# RS485.net
KiCad netlist of a schematic drawn in Altium Designer
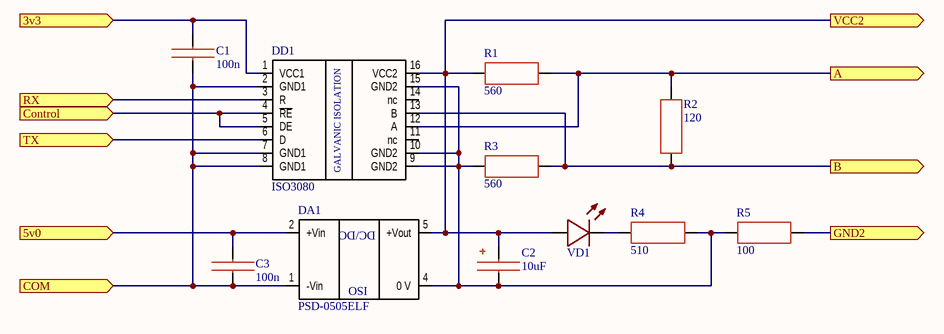
[diagram p0: RS485.SchDoc]

(export (version "E")
  (design (tool "Eeschema 10.0.6"))
  (components
    (comp (ref "C1")
      (value "100n")
      (footprint "Capacitor:CC0805_3D")
      (libsource (lib "Capacitor") (part "CC0805 X uF"))
    )
    (comp (ref "C2")
      (value "10uF")
      (footprint "Tantal Type C")
      (description "16 V")
      (libsource (lib "Capacitor") (part "Tantal C 10uF"))
    )
    (comp (ref "C3")
      (value "100n")
      (footprint "Capacitor:CC0805_3D")
      (libsource (lib "Capacitor") (part "CC0805 X uF"))
    )
    (comp (ref "DA1")
      (value "PSD-0505ELF")
      (footprint "PSD-xxxxELF")
      (description "PSD-xxxxELF")
      (libsource (lib "Rus_Library") (part "PSD-xxxxELF"))
    )
    (comp (ref "DD1")
      (value "ISO3080")
      (footprint "SO_16_W")
      (libsource (lib "Rus_Library") (part "ISO3080"))
    )
    (comp (ref "R1")
      (value "560")
      (footprint "Resistor:RC0805_3D")
      (libsource (lib "Resistor") (part "RC0805 X Ohm"))
    )
    (comp (ref "R2")
      (value "120")
      (footprint "Resistor:RC0805_3D")
      (libsource (lib "Resistor") (part "RC0805 X Ohm"))
    )
    (comp (ref "R3")
      (value "560")
      (footprint "Resistor:RC0805_3D")
      (libsource (lib "Resistor") (part "RC0805 X Ohm"))
    )
    (comp (ref "R4")
      (value "510")
      (footprint "Resistor:RC0805_3D")
      (libsource (lib "Resistor") (part "RC0805 X Ohm"))
    )
    (comp (ref "R5")
      (value "100")
      (footprint "Resistor:RC0805_3D")
      (libsource (lib "Resistor") (part "RC0805 X Ohm"))
    )
    (comp (ref "VD1")
      (value "Value")
      (footprint "KA-3021SGCT:2030")
      (libsource (lib "KA-3021SGCT") (part "KA-3021SGCT"))
    )
  )
  (nets
    (net (code "1") (name "/3v3") (class "Default")
      (node (ref "C1") (pin "2") (pinfunction "2_2") (pintype "passive"))
      (node (ref "DD1") (pin "1") (pinfunction "VCC1_1") (pintype "passive"))
    )
    (net (code "2") (name "/5v0") (class "Default")
      (node (ref "C3") (pin "2") (pinfunction "2_2") (pintype "passive"))
      (node (ref "DA1") (pin "2") (pinfunction "+Vin_2") (pintype "passive"))
    )
    (net (code "3") (name "/A") (class "Default")
      (node (ref "DD1") (pin "12") (pinfunction "A_12") (pintype "passive"))
      (node (ref "R1") (pin "2") (pinfunction "2_2") (pintype "passive"))
      (node (ref "R2") (pin "2") (pinfunction "2_2") (pintype "passive"))
    )
    (net (code "4") (name "/B") (class "Default")
      (node (ref "DD1") (pin "13") (pinfunction "B_13") (pintype "passive"))
      (node (ref "R2") (pin "1") (pinfunction "1_1") (pintype "passive"))
      (node (ref "R3") (pin "2") (pinfunction "2_2") (pintype "passive"))
    )
    (net (code "5") (name "/COM") (class "Default")
      (node (ref "C1") (pin "1") (pinfunction "1_1") (pintype "passive"))
      (node (ref "C3") (pin "1") (pinfunction "1_1") (pintype "passive"))
      (node (ref "DA1") (pin "1") (pinfunction "-Vin_1") (pintype "passive"))
      (node (ref "DD1") (pin "2") (pinfunction "GND1_2") (pintype "passive"))
      (node (ref "DD1") (pin "7") (pinfunction "GND1_7") (pintype "passive"))
      (node (ref "DD1") (pin "8") (pinfunction "GND1_8") (pintype "passive"))
    )
    (net (code "6") (name "/Control") (class "Default")
      (node (ref "DD1") (pin "4") (pinfunction "~{RE}_4") (pintype "passive"))
      (node (ref "DD1") (pin "5") (pinfunction "DE_5") (pintype "passive"))
    )
    (net (code "7") (name "/GND2") (class "Default")
      (node (ref "R5") (pin "2") (pinfunction "2_2") (pintype "passive"))
    )
    (net (code "8") (name "/RX") (class "Default")
      (node (ref "DD1") (pin "3") (pinfunction "R_3") (pintype "passive"))
    )
    (net (code "9") (name "/TX") (class "Default")
      (node (ref "DD1") (pin "6") (pinfunction "D_6") (pintype "passive"))
    )
    (net (code "10") (name "/VCC2") (class "Default")
      (node (ref "C2") (pin "2") (pinfunction "2_2") (pintype "passive"))
      (node (ref "DA1") (pin "5") (pinfunction "+Vout_5") (pintype "passive"))
      (node (ref "DD1") (pin "16") (pinfunction "VCC2_16") (pintype "passive"))
      (node (ref "R1") (pin "1") (pinfunction "1_1") (pintype "passive"))
      (node (ref "VD1") (pin "2") (pinfunction "2_2") (pintype "passive"))
    )
    (net (code "11") (name "Net-(DA1-0_V)") (class "Default")
      (node (ref "C2") (pin "1") (pinfunction "1_1") (pintype "passive"))
      (node (ref "DA1") (pin "4") (pinfunction "0_V_4") (pintype "passive"))
      (node (ref "DD1") (pin "10") (pinfunction "GND2_10") (pintype "passive"))
      (node (ref "DD1") (pin "15") (pinfunction "GND2_15") (pintype "passive"))
      (node (ref "DD1") (pin "9") (pinfunction "GND2_9") (pintype "passive"))
      (node (ref "R3") (pin "1") (pinfunction "1_1") (pintype "passive"))
      (node (ref "R4") (pin "1") (pinfunction "1_1") (pintype "passive"))
      (node (ref "R5") (pin "1") (pinfunction "1_1") (pintype "passive"))
    )
    (net (code "12") (name "Net-(R4-Pad2)") (class "Default")
      (node (ref "R4") (pin "2") (pinfunction "2_2") (pintype "passive"))
      (node (ref "VD1") (pin "1") (pinfunction "1_1") (pintype "passive"))
    )
    (net (code "13") (name "unconnected-(DA1-NC-Pad8)") (class "Default")
      (node (ref "DA1") (pin "8") (pinfunction "NC_8") (pintype "passive"))
    )
    (net (code "14") (name "unconnected-(DD1-nc-Pad11)") (class "Default")
      (node (ref "DD1") (pin "11") (pinfunction "nc_11") (pintype "passive"))
    )
    (net (code "15") (name "unconnected-(DD1-nc-Pad14)") (class "Default")
      (node (ref "DD1") (pin "14") (pinfunction "nc_14") (pintype "passive"))
    )
  )
)
